# config-ground.net
KiCad netlist of a schematic drawn in Altium Designer
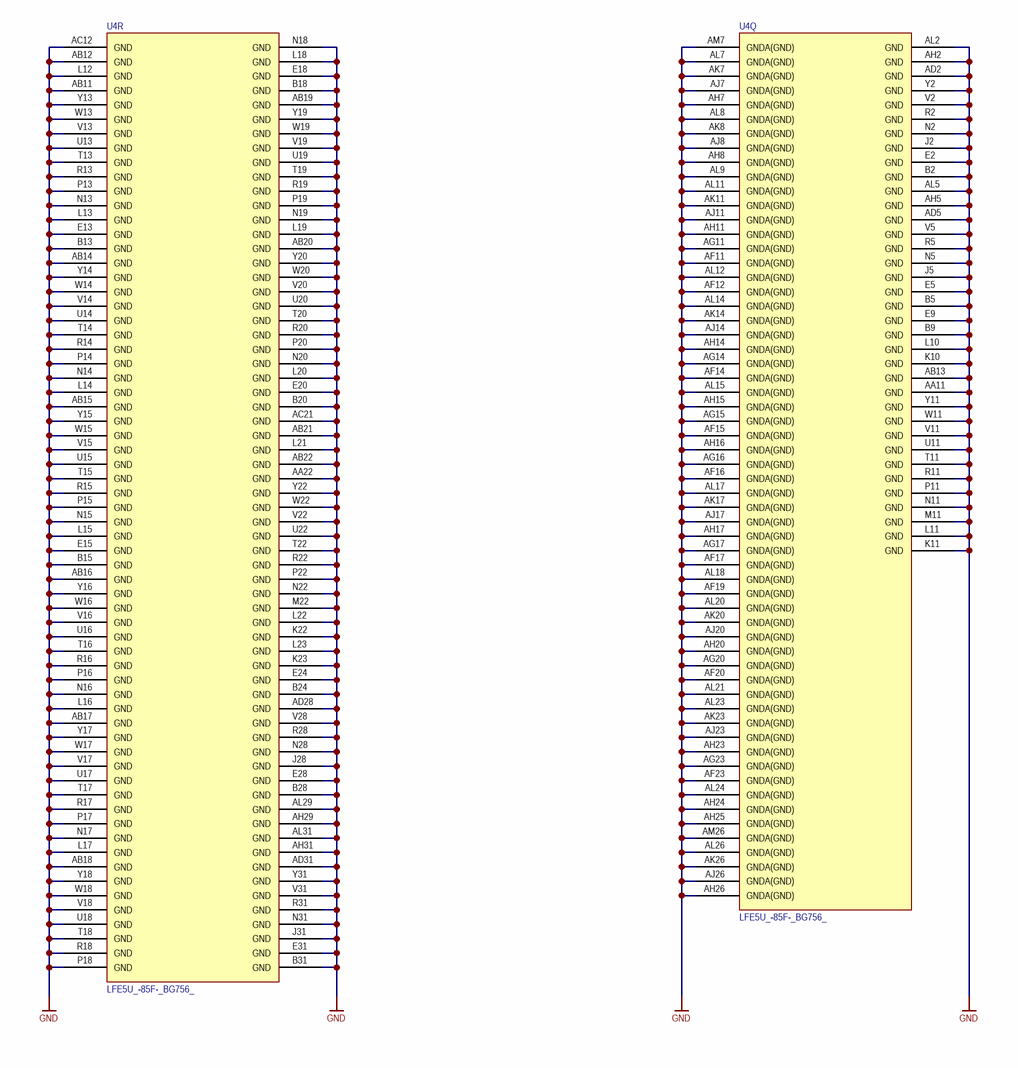
[diagram p0: config-ground.SchDoc]

(export (version "E")
  (design (tool "Eeschema 10.0.6"))
  (components
    (comp (ref "U4")
      (value "LFE5U_-85F-_BG756_")
      (footprint "lattice:caBGA756")
      (description "ECP5 FPGA, 85k LUT, 756-caBGA")
      (fields (field (name "MANUFACTURER") "Lattice Semiconductor"))
      (libsource (lib "lattice") (part "LFE5U_-85F-_BG756_"))
    )
  )
  (nets
    (net (code "1") (name "GND") (class "Default")
      (node (ref "U4") (pin "AA11") (pinfunction "GND_AA11") (pintype "power_in"))
      (node (ref "U4") (pin "AA22") (pinfunction "GND_AA22") (pintype "power_in"))
      (node (ref "U4") (pin "AB11") (pinfunction "GND_AB11") (pintype "power_in"))
      (node (ref "U4") (pin "AB12") (pinfunction "GND_AB12") (pintype "power_in"))
      (node (ref "U4") (pin "AB13") (pinfunction "GND_AB13") (pintype "power_in"))
      (node (ref "U4") (pin "AB14") (pinfunction "GND_AB14") (pintype "power_in"))
      (node (ref "U4") (pin "AB15") (pinfunction "GND_AB15") (pintype "power_in"))
      (node (ref "U4") (pin "AB16") (pinfunction "GND_AB16") (pintype "power_in"))
      (node (ref "U4") (pin "AB17") (pinfunction "GND_AB17") (pintype "power_in"))
      (node (ref "U4") (pin "AB18") (pinfunction "GND_AB18") (pintype "power_in"))
      (node (ref "U4") (pin "AB19") (pinfunction "GND_AB19") (pintype "power_in"))
      (node (ref "U4") (pin "AB20") (pinfunction "GND_AB20") (pintype "power_in"))
      (node (ref "U4") (pin "AB21") (pinfunction "GND_AB21") (pintype "power_in"))
      (node (ref "U4") (pin "AB22") (pinfunction "GND_AB22") (pintype "power_in"))
      (node (ref "U4") (pin "AC12") (pinfunction "GND_AC12") (pintype "power_in"))
      (node (ref "U4") (pin "AC21") (pinfunction "GND_AC21") (pintype "power_in"))
      (node (ref "U4") (pin "AD2") (pinfunction "GND_AD2") (pintype "power_in"))
      (node (ref "U4") (pin "AD28") (pinfunction "GND_AD28") (pintype "power_in"))
      (node (ref "U4") (pin "AD31") (pinfunction "GND_AD31") (pintype "power_in"))
      (node (ref "U4") (pin "AD5") (pinfunction "GND_AD5") (pintype "power_in"))
      (node (ref "U4") (pin "AF11") (pinfunction "GNDA(GND)_AF11") (pintype "power_in"))
      (node (ref "U4") (pin "AF12") (pinfunction "GNDA(GND)_AF12") (pintype "power_in"))
      (node (ref "U4") (pin "AF14") (pinfunction "GNDA(GND)_AF14") (pintype "power_in"))
      (node (ref "U4") (pin "AF15") (pinfunction "GNDA(GND)_AF15") (pintype "power_in"))
      (node (ref "U4") (pin "AF16") (pinfunction "GNDA(GND)_AF16") (pintype "power_in"))
      (node (ref "U4") (pin "AF17") (pinfunction "GNDA(GND)_AF17") (pintype "power_in"))
      (node (ref "U4") (pin "AF19") (pinfunction "GNDA(GND)_AF19") (pintype "power_in"))
      (node (ref "U4") (pin "AF20") (pinfunction "GNDA(GND)_AF20") (pintype "power_in"))
      (node (ref "U4") (pin "AF23") (pinfunction "GNDA(GND)_AF23") (pintype "power_in"))
      (node (ref "U4") (pin "AG11") (pinfunction "GNDA(GND)_AG11") (pintype "power_in"))
      (node (ref "U4") (pin "AG14") (pinfunction "GNDA(GND)_AG14") (pintype "power_in"))
      (node (ref "U4") (pin "AG15") (pinfunction "GNDA(GND)_AG15") (pintype "power_in"))
      (node (ref "U4") (pin "AG16") (pinfunction "GNDA(GND)_AG16") (pintype "power_in"))
      (node (ref "U4") (pin "AG17") (pinfunction "GNDA(GND)_AG17") (pintype "power_in"))
      (node (ref "U4") (pin "AG20") (pinfunction "GNDA(GND)_AG20") (pintype "power_in"))
      (node (ref "U4") (pin "AG23") (pinfunction "GNDA(GND)_AG23") (pintype "power_in"))
      (node (ref "U4") (pin "AH11") (pinfunction "GNDA(GND)_AH11") (pintype "power_in"))
      (node (ref "U4") (pin "AH14") (pinfunction "GNDA(GND)_AH14") (pintype "power_in"))
      (node (ref "U4") (pin "AH15") (pinfunction "GNDA(GND)_AH15") (pintype "power_in"))
      (node (ref "U4") (pin "AH16") (pinfunction "GNDA(GND)_AH16") (pintype "power_in"))
      (node (ref "U4") (pin "AH17") (pinfunction "GNDA(GND)_AH17") (pintype "power_in"))
      (node (ref "U4") (pin "AH2") (pinfunction "GND_AH2") (pintype "power_in"))
      (node (ref "U4") (pin "AH20") (pinfunction "GNDA(GND)_AH20") (pintype "power_in"))
      (node (ref "U4") (pin "AH23") (pinfunction "GNDA(GND)_AH23") (pintype "power_in"))
      (node (ref "U4") (pin "AH24") (pinfunction "GNDA(GND)_AH24") (pintype "power_in"))
      (node (ref "U4") (pin "AH25") (pinfunction "GNDA(GND)_AH25") (pintype "power_in"))
      (node (ref "U4") (pin "AH26") (pinfunction "GNDA(GND)_AH26") (pintype "power_in"))
      (node (ref "U4") (pin "AH29") (pinfunction "GND_AH29") (pintype "power_in"))
      (node (ref "U4") (pin "AH31") (pinfunction "GND_AH31") (pintype "power_in"))
      (node (ref "U4") (pin "AH5") (pinfunction "GND_AH5") (pintype "power_in"))
      (node (ref "U4") (pin "AH7") (pinfunction "GNDA(GND)_AH7") (pintype "power_in"))
      (node (ref "U4") (pin "AH8") (pinfunction "GNDA(GND)_AH8") (pintype "power_in"))
      (node (ref "U4") (pin "AJ11") (pinfunction "GNDA(GND)_AJ11") (pintype "power_in"))
      (node (ref "U4") (pin "AJ14") (pinfunction "GNDA(GND)_AJ14") (pintype "power_in"))
      (node (ref "U4") (pin "AJ17") (pinfunction "GNDA(GND)_AJ17") (pintype "power_in"))
      (node (ref "U4") (pin "AJ20") (pinfunction "GNDA(GND)_AJ20") (pintype "power_in"))
      (node (ref "U4") (pin "AJ23") (pinfunction "GNDA(GND)_AJ23") (pintype "power_in"))
      (node (ref "U4") (pin "AJ26") (pinfunction "GNDA(GND)_AJ26") (pintype "power_in"))
      (node (ref "U4") (pin "AJ7") (pinfunction "GNDA(GND)_AJ7") (pintype "power_in"))
      (node (ref "U4") (pin "AJ8") (pinfunction "GNDA(GND)_AJ8") (pintype "power_in"))
      (node (ref "U4") (pin "AK11") (pinfunction "GNDA(GND)_AK11") (pintype "power_in"))
      (node (ref "U4") (pin "AK14") (pinfunction "GNDA(GND)_AK14") (pintype "power_in"))
      (node (ref "U4") (pin "AK17") (pinfunction "GNDA(GND)_AK17") (pintype "power_in"))
      (node (ref "U4") (pin "AK20") (pinfunction "GNDA(GND)_AK20") (pintype "power_in"))
      (node (ref "U4") (pin "AK23") (pinfunction "GNDA(GND)_AK23") (pintype "power_in"))
      (node (ref "U4") (pin "AK26") (pinfunction "GNDA(GND)_AK26") (pintype "power_in"))
      (node (ref "U4") (pin "AK7") (pinfunction "GNDA(GND)_AK7") (pintype "power_in"))
      (node (ref "U4") (pin "AK8") (pinfunction "GNDA(GND)_AK8") (pintype "power_in"))
      (node (ref "U4") (pin "AL11") (pinfunction "GNDA(GND)_AL11") (pintype "power_in"))
      (node (ref "U4") (pin "AL12") (pinfunction "GNDA(GND)_AL12") (pintype "power_in"))
      (node (ref "U4") (pin "AL14") (pinfunction "GNDA(GND)_AL14") (pintype "power_in"))
      (node (ref "U4") (pin "AL15") (pinfunction "GNDA(GND)_AL15") (pintype "power_in"))
      (node (ref "U4") (pin "AL17") (pinfunction "GNDA(GND)_AL17") (pintype "power_in"))
      (node (ref "U4") (pin "AL18") (pinfunction "GNDA(GND)_AL18") (pintype "power_in"))
      (node (ref "U4") (pin "AL2") (pinfunction "GND_AL2") (pintype "power_in"))
      (node (ref "U4") (pin "AL20") (pinfunction "GNDA(GND)_AL20") (pintype "power_in"))
      (node (ref "U4") (pin "AL21") (pinfunction "GNDA(GND)_AL21") (pintype "power_in"))
      (node (ref "U4") (pin "AL23") (pinfunction "GNDA(GND)_AL23") (pintype "power_in"))
      (node (ref "U4") (pin "AL24") (pinfunction "GNDA(GND)_AL24") (pintype "power_in"))
      (node (ref "U4") (pin "AL26") (pinfunction "GNDA(GND)_AL26") (pintype "power_in"))
      (node (ref "U4") (pin "AL29") (pinfunction "GND_AL29") (pintype "power_in"))
      (node (ref "U4") (pin "AL31") (pinfunction "GND_AL31") (pintype "power_in"))
      (node (ref "U4") (pin "AL5") (pinfunction "GND_AL5") (pintype "power_in"))
      (node (ref "U4") (pin "AL7") (pinfunction "GNDA(GND)_AL7") (pintype "power_in"))
      (node (ref "U4") (pin "AL8") (pinfunction "GNDA(GND)_AL8") (pintype "power_in"))
      (node (ref "U4") (pin "AL9") (pinfunction "GNDA(GND)_AL9") (pintype "power_in"))
      (node (ref "U4") (pin "AM26") (pinfunction "GNDA(GND)_AM26") (pintype "power_in"))
      (node (ref "U4") (pin "AM7") (pinfunction "GNDA(GND)_AM7") (pintype "power_in"))
      (node (ref "U4") (pin "B13") (pinfunction "GND_B13") (pintype "power_in"))
      (node (ref "U4") (pin "B15") (pinfunction "GND_B15") (pintype "power_in"))
      (node (ref "U4") (pin "B18") (pinfunction "GND_B18") (pintype "power_in"))
      (node (ref "U4") (pin "B2") (pinfunction "GND_B2") (pintype "power_in"))
      (node (ref "U4") (pin "B20") (pinfunction "GND_B20") (pintype "power_in"))
      (node (ref "U4") (pin "B24") (pinfunction "GND_B24") (pintype "power_in"))
      (node (ref "U4") (pin "B28") (pinfunction "GND_B28") (pintype "power_in"))
      (node (ref "U4") (pin "B31") (pinfunction "GND_B31") (pintype "power_in"))
      (node (ref "U4") (pin "B5") (pinfunction "GND_B5") (pintype "power_in"))
      (node (ref "U4") (pin "B9") (pinfunction "GND_B9") (pintype "power_in"))
      (node (ref "U4") (pin "E13") (pinfunction "GND_E13") (pintype "power_in"))
      (node (ref "U4") (pin "E15") (pinfunction "GND_E15") (pintype "power_in"))
      (node (ref "U4") (pin "E18") (pinfunction "GND_E18") (pintype "power_in"))
      (node (ref "U4") (pin "E2") (pinfunction "GND_E2") (pintype "power_in"))
      (node (ref "U4") (pin "E20") (pinfunction "GND_E20") (pintype "power_in"))
      (node (ref "U4") (pin "E24") (pinfunction "GND_E24") (pintype "power_in"))
      (node (ref "U4") (pin "E28") (pinfunction "GND_E28") (pintype "power_in"))
      (node (ref "U4") (pin "E31") (pinfunction "GND_E31") (pintype "power_in"))
      (node (ref "U4") (pin "E5") (pinfunction "GND_E5") (pintype "power_in"))
      (node (ref "U4") (pin "E9") (pinfunction "GND_E9") (pintype "power_in"))
      (node (ref "U4") (pin "J2") (pinfunction "GND_J2") (pintype "power_in"))
      (node (ref "U4") (pin "J28") (pinfunction "GND_J28") (pintype "power_in"))
      (node (ref "U4") (pin "J31") (pinfunction "GND_J31") (pintype "power_in"))
      (node (ref "U4") (pin "J5") (pinfunction "GND_J5") (pintype "power_in"))
      (node (ref "U4") (pin "K10") (pinfunction "GND_K10") (pintype "power_in"))
      (node (ref "U4") (pin "K11") (pinfunction "GND_K11") (pintype "power_in"))
      (node (ref "U4") (pin "K22") (pinfunction "GND_K22") (pintype "power_in"))
      (node (ref "U4") (pin "K23") (pinfunction "GND_K23") (pintype "power_in"))
      (node (ref "U4") (pin "L10") (pinfunction "GND_L10") (pintype "power_in"))
      (node (ref "U4") (pin "L11") (pinfunction "GND_L11") (pintype "power_in"))
      (node (ref "U4") (pin "L12") (pinfunction "GND_L12") (pintype "power_in"))
      (node (ref "U4") (pin "L13") (pinfunction "GND_L13") (pintype "power_in"))
      (node (ref "U4") (pin "L14") (pinfunction "GND_L14") (pintype "power_in"))
      (node (ref "U4") (pin "L15") (pinfunction "GND_L15") (pintype "power_in"))
      (node (ref "U4") (pin "L16") (pinfunction "GND_L16") (pintype "power_in"))
      (node (ref "U4") (pin "L17") (pinfunction "GND_L17") (pintype "power_in"))
      (node (ref "U4") (pin "L18") (pinfunction "GND_L18") (pintype "power_in"))
      (node (ref "U4") (pin "L19") (pinfunction "GND_L19") (pintype "power_in"))
      (node (ref "U4") (pin "L20") (pinfunction "GND_L20") (pintype "power_in"))
      (node (ref "U4") (pin "L21") (pinfunction "GND_L21") (pintype "power_in"))
      (node (ref "U4") (pin "L22") (pinfunction "GND_L22") (pintype "power_in"))
      (node (ref "U4") (pin "L23") (pinfunction "GND_L23") (pintype "power_in"))
      (node (ref "U4") (pin "M11") (pinfunction "GND_M11") (pintype "power_in"))
      (node (ref "U4") (pin "M22") (pinfunction "GND_M22") (pintype "power_in"))
      (node (ref "U4") (pin "N11") (pinfunction "GND_N11") (pintype "power_in"))
      (node (ref "U4") (pin "N13") (pinfunction "GND_N13") (pintype "power_in"))
      (node (ref "U4") (pin "N14") (pinfunction "GND_N14") (pintype "power_in"))
      (node (ref "U4") (pin "N15") (pinfunction "GND_N15") (pintype "power_in"))
      (node (ref "U4") (pin "N16") (pinfunction "GND_N16") (pintype "power_in"))
      (node (ref "U4") (pin "N17") (pinfunction "GND_N17") (pintype "power_in"))
      (node (ref "U4") (pin "N18") (pinfunction "GND_N18") (pintype "power_in"))
      (node (ref "U4") (pin "N19") (pinfunction "GND_N19") (pintype "power_in"))
      (node (ref "U4") (pin "N2") (pinfunction "GND_N2") (pintype "power_in"))
      (node (ref "U4") (pin "N20") (pinfunction "GND_N20") (pintype "power_in"))
      (node (ref "U4") (pin "N22") (pinfunction "GND_N22") (pintype "power_in"))
      (node (ref "U4") (pin "N28") (pinfunction "GND_N28") (pintype "power_in"))
      (node (ref "U4") (pin "N31") (pinfunction "GND_N31") (pintype "power_in"))
      (node (ref "U4") (pin "N5") (pinfunction "GND_N5") (pintype "power_in"))
      (node (ref "U4") (pin "P11") (pinfunction "GND_P11") (pintype "power_in"))
      (node (ref "U4") (pin "P13") (pinfunction "GND_P13") (pintype "power_in"))
      (node (ref "U4") (pin "P14") (pinfunction "GND_P14") (pintype "power_in"))
      (node (ref "U4") (pin "P15") (pinfunction "GND_P15") (pintype "power_in"))
      (node (ref "U4") (pin "P16") (pinfunction "GND_P16") (pintype "power_in"))
      (node (ref "U4") (pin "P17") (pinfunction "GND_P17") (pintype "power_in"))
      (node (ref "U4") (pin "P18") (pinfunction "GND_P18") (pintype "power_in"))
      (node (ref "U4") (pin "P19") (pinfunction "GND_P19") (pintype "power_in"))
      (node (ref "U4") (pin "P20") (pinfunction "GND_P20") (pintype "power_in"))
      (node (ref "U4") (pin "P22") (pinfunction "GND_P22") (pintype "power_in"))
      (node (ref "U4") (pin "R11") (pinfunction "GND_R11") (pintype "power_in"))
      (node (ref "U4") (pin "R13") (pinfunction "GND_R13") (pintype "power_in"))
      (node (ref "U4") (pin "R14") (pinfunction "GND_R14") (pintype "power_in"))
      (node (ref "U4") (pin "R15") (pinfunction "GND_R15") (pintype "power_in"))
      (node (ref "U4") (pin "R16") (pinfunction "GND_R16") (pintype "power_in"))
      (node (ref "U4") (pin "R17") (pinfunction "GND_R17") (pintype "power_in"))
      (node (ref "U4") (pin "R18") (pinfunction "GND_R18") (pintype "power_in"))
      (node (ref "U4") (pin "R19") (pinfunction "GND_R19") (pintype "power_in"))
      (node (ref "U4") (pin "R2") (pinfunction "GND_R2") (pintype "power_in"))
      (node (ref "U4") (pin "R20") (pinfunction "GND_R20") (pintype "power_in"))
      (node (ref "U4") (pin "R22") (pinfunction "GND_R22") (pintype "power_in"))
      (node (ref "U4") (pin "R28") (pinfunction "GND_R28") (pintype "power_in"))
      (node (ref "U4") (pin "R31") (pinfunction "GND_R31") (pintype "power_in"))
      (node (ref "U4") (pin "R5") (pinfunction "GND_R5") (pintype "power_in"))
      (node (ref "U4") (pin "T11") (pinfunction "GND_T11") (pintype "power_in"))
      (node (ref "U4") (pin "T13") (pinfunction "GND_T13") (pintype "power_in"))
      (node (ref "U4") (pin "T14") (pinfunction "GND_T14") (pintype "power_in"))
      (node (ref "U4") (pin "T15") (pinfunction "GND_T15") (pintype "power_in"))
      (node (ref "U4") (pin "T16") (pinfunction "GND_T16") (pintype "power_in"))
      (node (ref "U4") (pin "T17") (pinfunction "GND_T17") (pintype "power_in"))
      (node (ref "U4") (pin "T18") (pinfunction "GND_T18") (pintype "power_in"))
      (node (ref "U4") (pin "T19") (pinfunction "GND_T19") (pintype "power_in"))
      (node (ref "U4") (pin "T20") (pinfunction "GND_T20") (pintype "power_in"))
      (node (ref "U4") (pin "T22") (pinfunction "GND_T22") (pintype "power_in"))
      (node (ref "U4") (pin "U11") (pinfunction "GND_U11") (pintype "power_in"))
      (node (ref "U4") (pin "U13") (pinfunction "GND_U13") (pintype "power_in"))
      (node (ref "U4") (pin "U14") (pinfunction "GND_U14") (pintype "power_in"))
      (node (ref "U4") (pin "U15") (pinfunction "GND_U15") (pintype "power_in"))
      (node (ref "U4") (pin "U16") (pinfunction "GND_U16") (pintype "power_in"))
      (node (ref "U4") (pin "U17") (pinfunction "GND_U17") (pintype "power_in"))
      (node (ref "U4") (pin "U18") (pinfunction "GND_U18") (pintype "power_in"))
      (node (ref "U4") (pin "U19") (pinfunction "GND_U19") (pintype "power_in"))
      (node (ref "U4") (pin "U20") (pinfunction "GND_U20") (pintype "power_in"))
      (node (ref "U4") (pin "U22") (pinfunction "GND_U22") (pintype "power_in"))
      (node (ref "U4") (pin "V11") (pinfunction "GND_V11") (pintype "power_in"))
      (node (ref "U4") (pin "V13") (pinfunction "GND_V13") (pintype "power_in"))
      (node (ref "U4") (pin "V14") (pinfunction "GND_V14") (pintype "power_in"))
      (node (ref "U4") (pin "V15") (pinfunction "GND_V15") (pintype "power_in"))
      (node (ref "U4") (pin "V16") (pinfunction "GND_V16") (pintype "power_in"))
      (node (ref "U4") (pin "V17") (pinfunction "GND_V17") (pintype "power_in"))
      (node (ref "U4") (pin "V18") (pinfunction "GND_V18") (pintype "power_in"))
      (node (ref "U4") (pin "V19") (pinfunction "GND_V19") (pintype "power_in"))
      (node (ref "U4") (pin "V2") (pinfunction "GND_V2") (pintype "power_in"))
      (node (ref "U4") (pin "V20") (pinfunction "GND_V20") (pintype "power_in"))
      (node (ref "U4") (pin "V22") (pinfunction "GND_V22") (pintype "power_in"))
      (node (ref "U4") (pin "V28") (pinfunction "GND_V28") (pintype "power_in"))
      (node (ref "U4") (pin "V31") (pinfunction "GND_V31") (pintype "power_in"))
      (node (ref "U4") (pin "V5") (pinfunction "GND_V5") (pintype "power_in"))
      (node (ref "U4") (pin "W11") (pinfunction "GND_W11") (pintype "power_in"))
      (node (ref "U4") (pin "W13") (pinfunction "GND_W13") (pintype "power_in"))
      (node (ref "U4") (pin "W14") (pinfunction "GND_W14") (pintype "power_in"))
      (node (ref "U4") (pin "W15") (pinfunction "GND_W15") (pintype "power_in"))
      (node (ref "U4") (pin "W16") (pinfunction "GND_W16") (pintype "power_in"))
      (node (ref "U4") (pin "W17") (pinfunction "GND_W17") (pintype "power_in"))
      (node (ref "U4") (pin "W18") (pinfunction "GND_W18") (pintype "power_in"))
      (node (ref "U4") (pin "W19") (pinfunction "GND_W19") (pintype "power_in"))
      (node (ref "U4") (pin "W20") (pinfunction "GND_W20") (pintype "power_in"))
      (node (ref "U4") (pin "W22") (pinfunction "GND_W22") (pintype "power_in"))
      (node (ref "U4") (pin "Y11") (pinfunction "GND_Y11") (pintype "power_in"))
      (node (ref "U4") (pin "Y13") (pinfunction "GND_Y13") (pintype "power_in"))
      (node (ref "U4") (pin "Y14") (pinfunction "GND_Y14") (pintype "power_in"))
      (node (ref "U4") (pin "Y15") (pinfunction "GND_Y15") (pintype "power_in"))
      (node (ref "U4") (pin "Y16") (pinfunction "GND_Y16") (pintype "power_in"))
      (node (ref "U4") (pin "Y17") (pinfunction "GND_Y17") (pintype "power_in"))
      (node (ref "U4") (pin "Y18") (pinfunction "GND_Y18") (pintype "power_in"))
      (node (ref "U4") (pin "Y19") (pinfunction "GND_Y19") (pintype "power_in"))
      (node (ref "U4") (pin "Y2") (pinfunction "GND_Y2") (pintype "power_in"))
      (node (ref "U4") (pin "Y20") (pinfunction "GND_Y20") (pintype "power_in"))
      (node (ref "U4") (pin "Y22") (pinfunction "GND_Y22") (pintype "power_in"))
      (node (ref "U4") (pin "Y31") (pinfunction "GND_Y31") (pintype "power_in"))
    )
  )
)
